# BoardB.net
KiCad netlist of a schematic drawn in Altium Designer
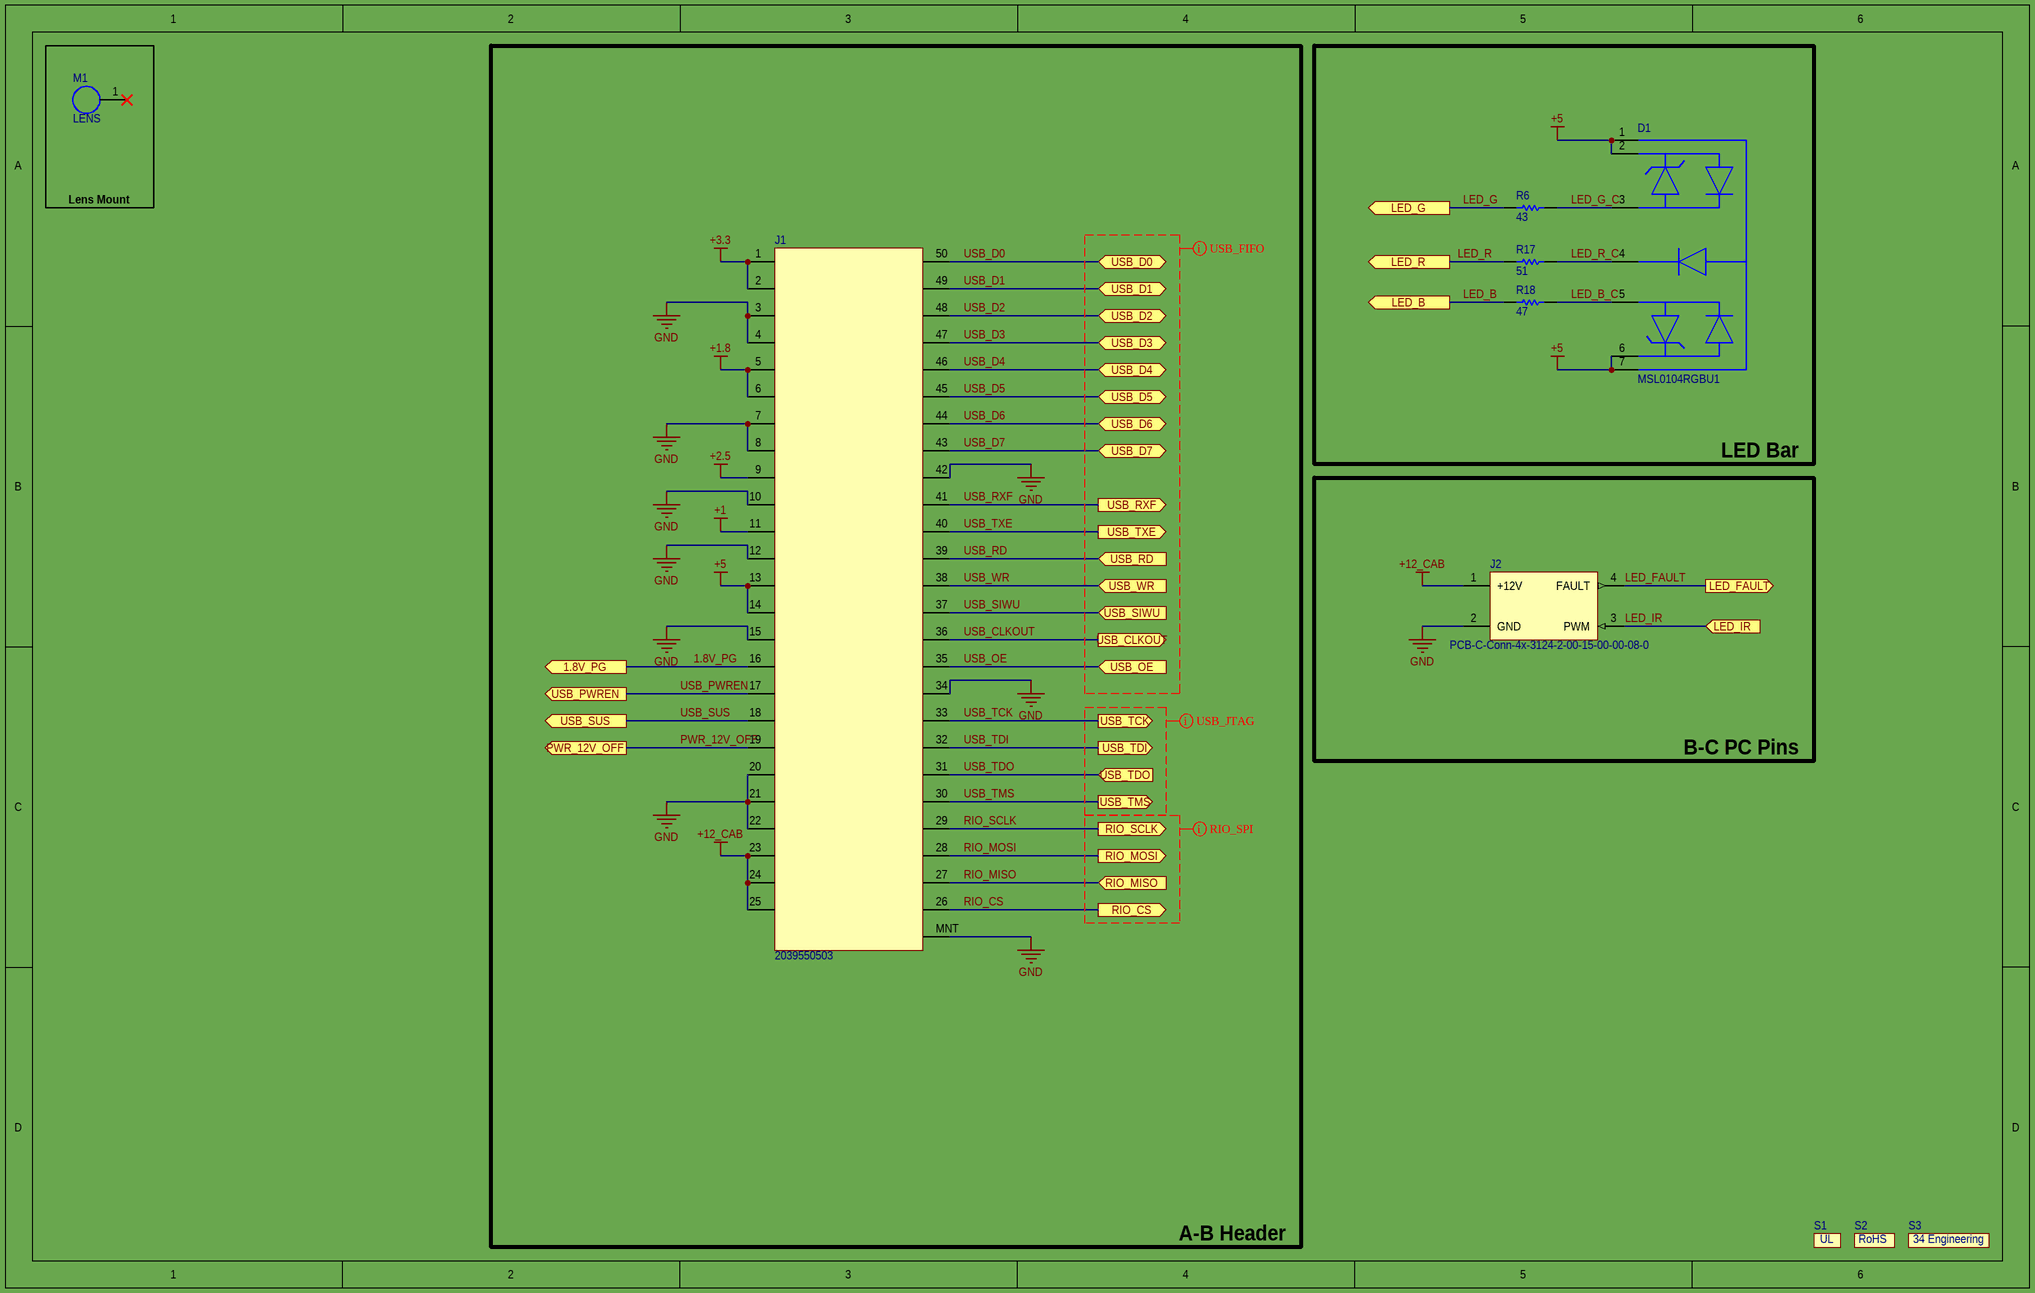
[diagram p0: BoardB.SchDoc]

(export (version "E")
  (design (tool "Eeschema 10.0.6"))
  (components
    (comp (ref "D1")
      (value "MSL0104RGBU1")
      (footprint "FP-MSL0104-MFG")
      (description "LED RGB DIFFUSED 2709 SMD R/A")
      (fields
        (field (name "OCTOPART") "https://octopart.com/msl0104rgbu1-rohm-71139759")
        (field (name "MANUFACTURER") "Rohm")
      )
      (libsource (lib "Altium Content Vault") (part "c1ae77389a615bb85b9424d60117df8"))
    )
    (comp (ref "J1")
      (value "2039550503")
      (footprint "2039550503")
      (fields (field (name "MANUFACTURER") "Molex") (field (name "MANUFACTURER PART NUMBER") "203955-0503"))
      (libsource (lib "Virtex") (part "2039550503"))
    )
    (comp (ref "J2")
      (value "PCB-C-Conn-4x-3124-2-00-15-00-00-08-0")
      (footprint "PCB-C-Conn-4x-3124-2-00-15-00-00-08-0")
      (libsource (lib "Virtex") (part "PCB-C-Conn-4x-3124-2-00-15-00-00-08-0"))
    )
    (comp (ref "M1") (value "LENS") (footprint "LENS_MNT") (libsource (lib "BoardB") (part "LENS_MNT")))
    (comp (ref "R6")
      (value "43")
      (footprint "RESC0603X26X15ML03T05")
      (fields (field (name "MANUFACTURER") "Panasonic") (field (name "PART NUMBER") "ERJ1GNF43R0C"))
      (libsource (lib "Altium Content Vault") (part "RES"))
    )
    (comp (ref "R17")
      (value "51")
      (footprint "RESC1608X55X30NL15T15")
      (fields (field (name "PART NUMBER") "ERJ3EKF51R0V") (field (name "MANUFACTURER") "Panasonic"))
      (libsource (lib "Altium Content Vault") (part "RES"))
    )
    (comp (ref "R18")
      (value "47")
      (footprint "RESC1608X55X30NL15T15")
      (description "Chip Resistor, 47 Ohm, +/- 1%, 0.1 W, -55 to 155 degC, 0603 (1608 Metric), RoHS, Tape and Reel")
      (fields (field (name "TOLERANCE") "1%"))
      (libsource (lib "Altium Content Vault") (part "RES-2"))
    )
    (comp (ref "S1") (value "~") (footprint "UL") (libsource (lib "Virtex") (part "UL")))
    (comp (ref "S2") (value "~") (footprint "RoHS") (libsource (lib "Virtex") (part "RoHS")))
    (comp (ref "S3")
      (value "~")
      (footprint "34EngineeringLogo")
      (description "34 Engineering Silkscreen Logo")
      (libsource (lib "Virtex") (part "34EngineeringLogo"))
    )
  )
  (nets
    (net (code "1") (name "+1") (class "Default") (node (ref "J1") (pin "11") (pintype "passive")))
    (net (code "2") (name "+1.8") (class "Default")
      (node (ref "J1") (pin "5") (pintype "passive"))
      (node (ref "J1") (pin "6") (pintype "passive"))
    )
    (net (code "3") (name "+2.5") (class "Default") (node (ref "J1") (pin "9") (pintype "passive")))
    (net (code "4") (name "+3.3") (class "Default")
      (node (ref "J1") (pin "1") (pintype "passive"))
      (node (ref "J1") (pin "2") (pintype "passive"))
    )
    (net (code "5") (name "+5") (class "Default")
      (node (ref "D1") (pin "1") (pinfunction "R_A_1") (pintype "passive"))
      (node (ref "D1") (pin "2") (pinfunction "G_A_2") (pintype "passive"))
      (node (ref "D1") (pin "6") (pinfunction "B_A_6") (pintype "passive"))
      (node (ref "D1") (pin "7") (pinfunction "R_A_7") (pintype "passive"))
      (node (ref "J1") (pin "13") (pintype "passive"))
      (node (ref "J1") (pin "14") (pintype "passive"))
    )
    (net (code "6") (name "+12_CAB") (class "Default")
      (node (ref "J1") (pin "23") (pintype "passive"))
      (node (ref "J1") (pin "24") (pintype "passive"))
      (node (ref "J1") (pin "25") (pintype "passive"))
      (node (ref "J2") (pin "1") (pinfunction "+12V_1") (pintype "power_in"))
    )
    (net (code "7") (name "/1.8V_PG") (class "Default") (node (ref "J1") (pin "16") (pintype "passive")))
    (net (code "8") (name "/LED_B") (class "Default")
      (node (ref "R18") (pin "1") (pinfunction "1_1") (pintype "passive"))
    )
    (net (code "9") (name "/LED_B_C") (class "Default")
      (node (ref "D1") (pin "5") (pinfunction "B_K_5") (pintype "passive"))
      (node (ref "R18") (pin "2") (pinfunction "2_2") (pintype "passive"))
    )
    (net (code "10") (name "/LED_FAULT") (class "Default")
      (node (ref "J2") (pin "4") (pinfunction "FAULT_4") (pintype "output"))
    )
    (net (code "11") (name "/LED_G") (class "Default")
      (node (ref "R6") (pin "1") (pinfunction "1_1") (pintype "passive"))
    )
    (net (code "12") (name "/LED_G_C") (class "Default")
      (node (ref "D1") (pin "3") (pinfunction "G_K_3") (pintype "passive"))
      (node (ref "R6") (pin "2") (pinfunction "2_2") (pintype "passive"))
    )
    (net (code "13") (name "/LED_IR") (class "Default")
      (node (ref "J2") (pin "3") (pinfunction "PWM_3") (pintype "input"))
    )
    (net (code "14") (name "/LED_R") (class "Default")
      (node (ref "R17") (pin "1") (pinfunction "1_1") (pintype "passive"))
    )
    (net (code "15") (name "/LED_R_C") (class "Default")
      (node (ref "D1") (pin "4") (pinfunction "R_K_4") (pintype "passive"))
      (node (ref "R17") (pin "2") (pinfunction "2_2") (pintype "passive"))
    )
    (net (code "16") (name "/PWR_12V_OFF") (class "Default") (node (ref "J1") (pin "19") (pintype "passive")))
    (net (code "17") (name "/RIO_CS") (class "Default") (node (ref "J1") (pin "26") (pintype "passive")))
    (net (code "18") (name "/RIO_MISO") (class "Default") (node (ref "J1") (pin "27") (pintype "passive")))
    (net (code "19") (name "/RIO_MOSI") (class "Default") (node (ref "J1") (pin "28") (pintype "passive")))
    (net (code "20") (name "/RIO_SCLK") (class "Default") (node (ref "J1") (pin "29") (pintype "passive")))
    (net (code "21") (name "/USB_CLKOUT") (class "Default") (node (ref "J1") (pin "36") (pintype "passive")))
    (net (code "22") (name "/USB_D0") (class "Default") (node (ref "J1") (pin "50") (pintype "passive")))
    (net (code "23") (name "/USB_D1") (class "Default") (node (ref "J1") (pin "49") (pintype "passive")))
    (net (code "24") (name "/USB_D2") (class "Default") (node (ref "J1") (pin "48") (pintype "passive")))
    (net (code "25") (name "/USB_D3") (class "Default") (node (ref "J1") (pin "47") (pintype "passive")))
    (net (code "26") (name "/USB_D4") (class "Default") (node (ref "J1") (pin "46") (pintype "passive")))
    (net (code "27") (name "/USB_D5") (class "Default") (node (ref "J1") (pin "45") (pintype "passive")))
    (net (code "28") (name "/USB_D6") (class "Default") (node (ref "J1") (pin "44") (pintype "passive")))
    (net (code "29") (name "/USB_D7") (class "Default") (node (ref "J1") (pin "43") (pintype "passive")))
    (net (code "30") (name "/USB_OE") (class "Default") (node (ref "J1") (pin "35") (pintype "passive")))
    (net (code "31") (name "/USB_PWREN") (class "Default") (node (ref "J1") (pin "17") (pintype "passive")))
    (net (code "32") (name "/USB_RD") (class "Default") (node (ref "J1") (pin "39") (pintype "passive")))
    (net (code "33") (name "/USB_RXF") (class "Default") (node (ref "J1") (pin "41") (pintype "passive")))
    (net (code "34") (name "/USB_SIWU") (class "Default") (node (ref "J1") (pin "37") (pintype "passive")))
    (net (code "35") (name "/USB_SUS") (class "Default") (node (ref "J1") (pin "18") (pintype "passive")))
    (net (code "36") (name "/USB_TCK") (class "Default") (node (ref "J1") (pin "33") (pintype "passive")))
    (net (code "37") (name "/USB_TDI") (class "Default") (node (ref "J1") (pin "32") (pintype "passive")))
    (net (code "38") (name "/USB_TDO") (class "Default") (node (ref "J1") (pin "31") (pintype "passive")))
    (net (code "39") (name "/USB_TMS") (class "Default") (node (ref "J1") (pin "30") (pintype "passive")))
    (net (code "40") (name "/USB_TXE") (class "Default") (node (ref "J1") (pin "40") (pintype "passive")))
    (net (code "41") (name "/USB_WR") (class "Default") (node (ref "J1") (pin "38") (pintype "passive")))
    (net (code "42") (name "GND") (class "Default")
      (node (ref "J1") (pin "10") (pintype "passive"))
      (node (ref "J1") (pin "12") (pintype "passive"))
      (node (ref "J1") (pin "15") (pintype "passive"))
      (node (ref "J1") (pin "20") (pintype "passive"))
      (node (ref "J1") (pin "21") (pintype "passive"))
      (node (ref "J1") (pin "22") (pintype "passive"))
      (node (ref "J1") (pin "3") (pintype "passive"))
      (node (ref "J1") (pin "34") (pintype "passive"))
      (node (ref "J1") (pin "4") (pintype "passive"))
      (node (ref "J1") (pin "42") (pintype "passive"))
      (node (ref "J1") (pin "7") (pintype "passive"))
      (node (ref "J1") (pin "8") (pintype "passive"))
      (node (ref "J1") (pin "MNT") (pintype "passive"))
      (node (ref "J2") (pin "2") (pinfunction "GND_2") (pintype "power_in"))
    )
    (net (code "43") (name "unconnected-(M1-Pad1)") (class "Default")
      (node (ref "M1") (pin "1") (pintype "passive+no_connect"))
    )
  )
)
